# ProPrj_Fallout_card_2026-06-26.net
KiCad netlist of a schematic drawn in EasyEDA Pro
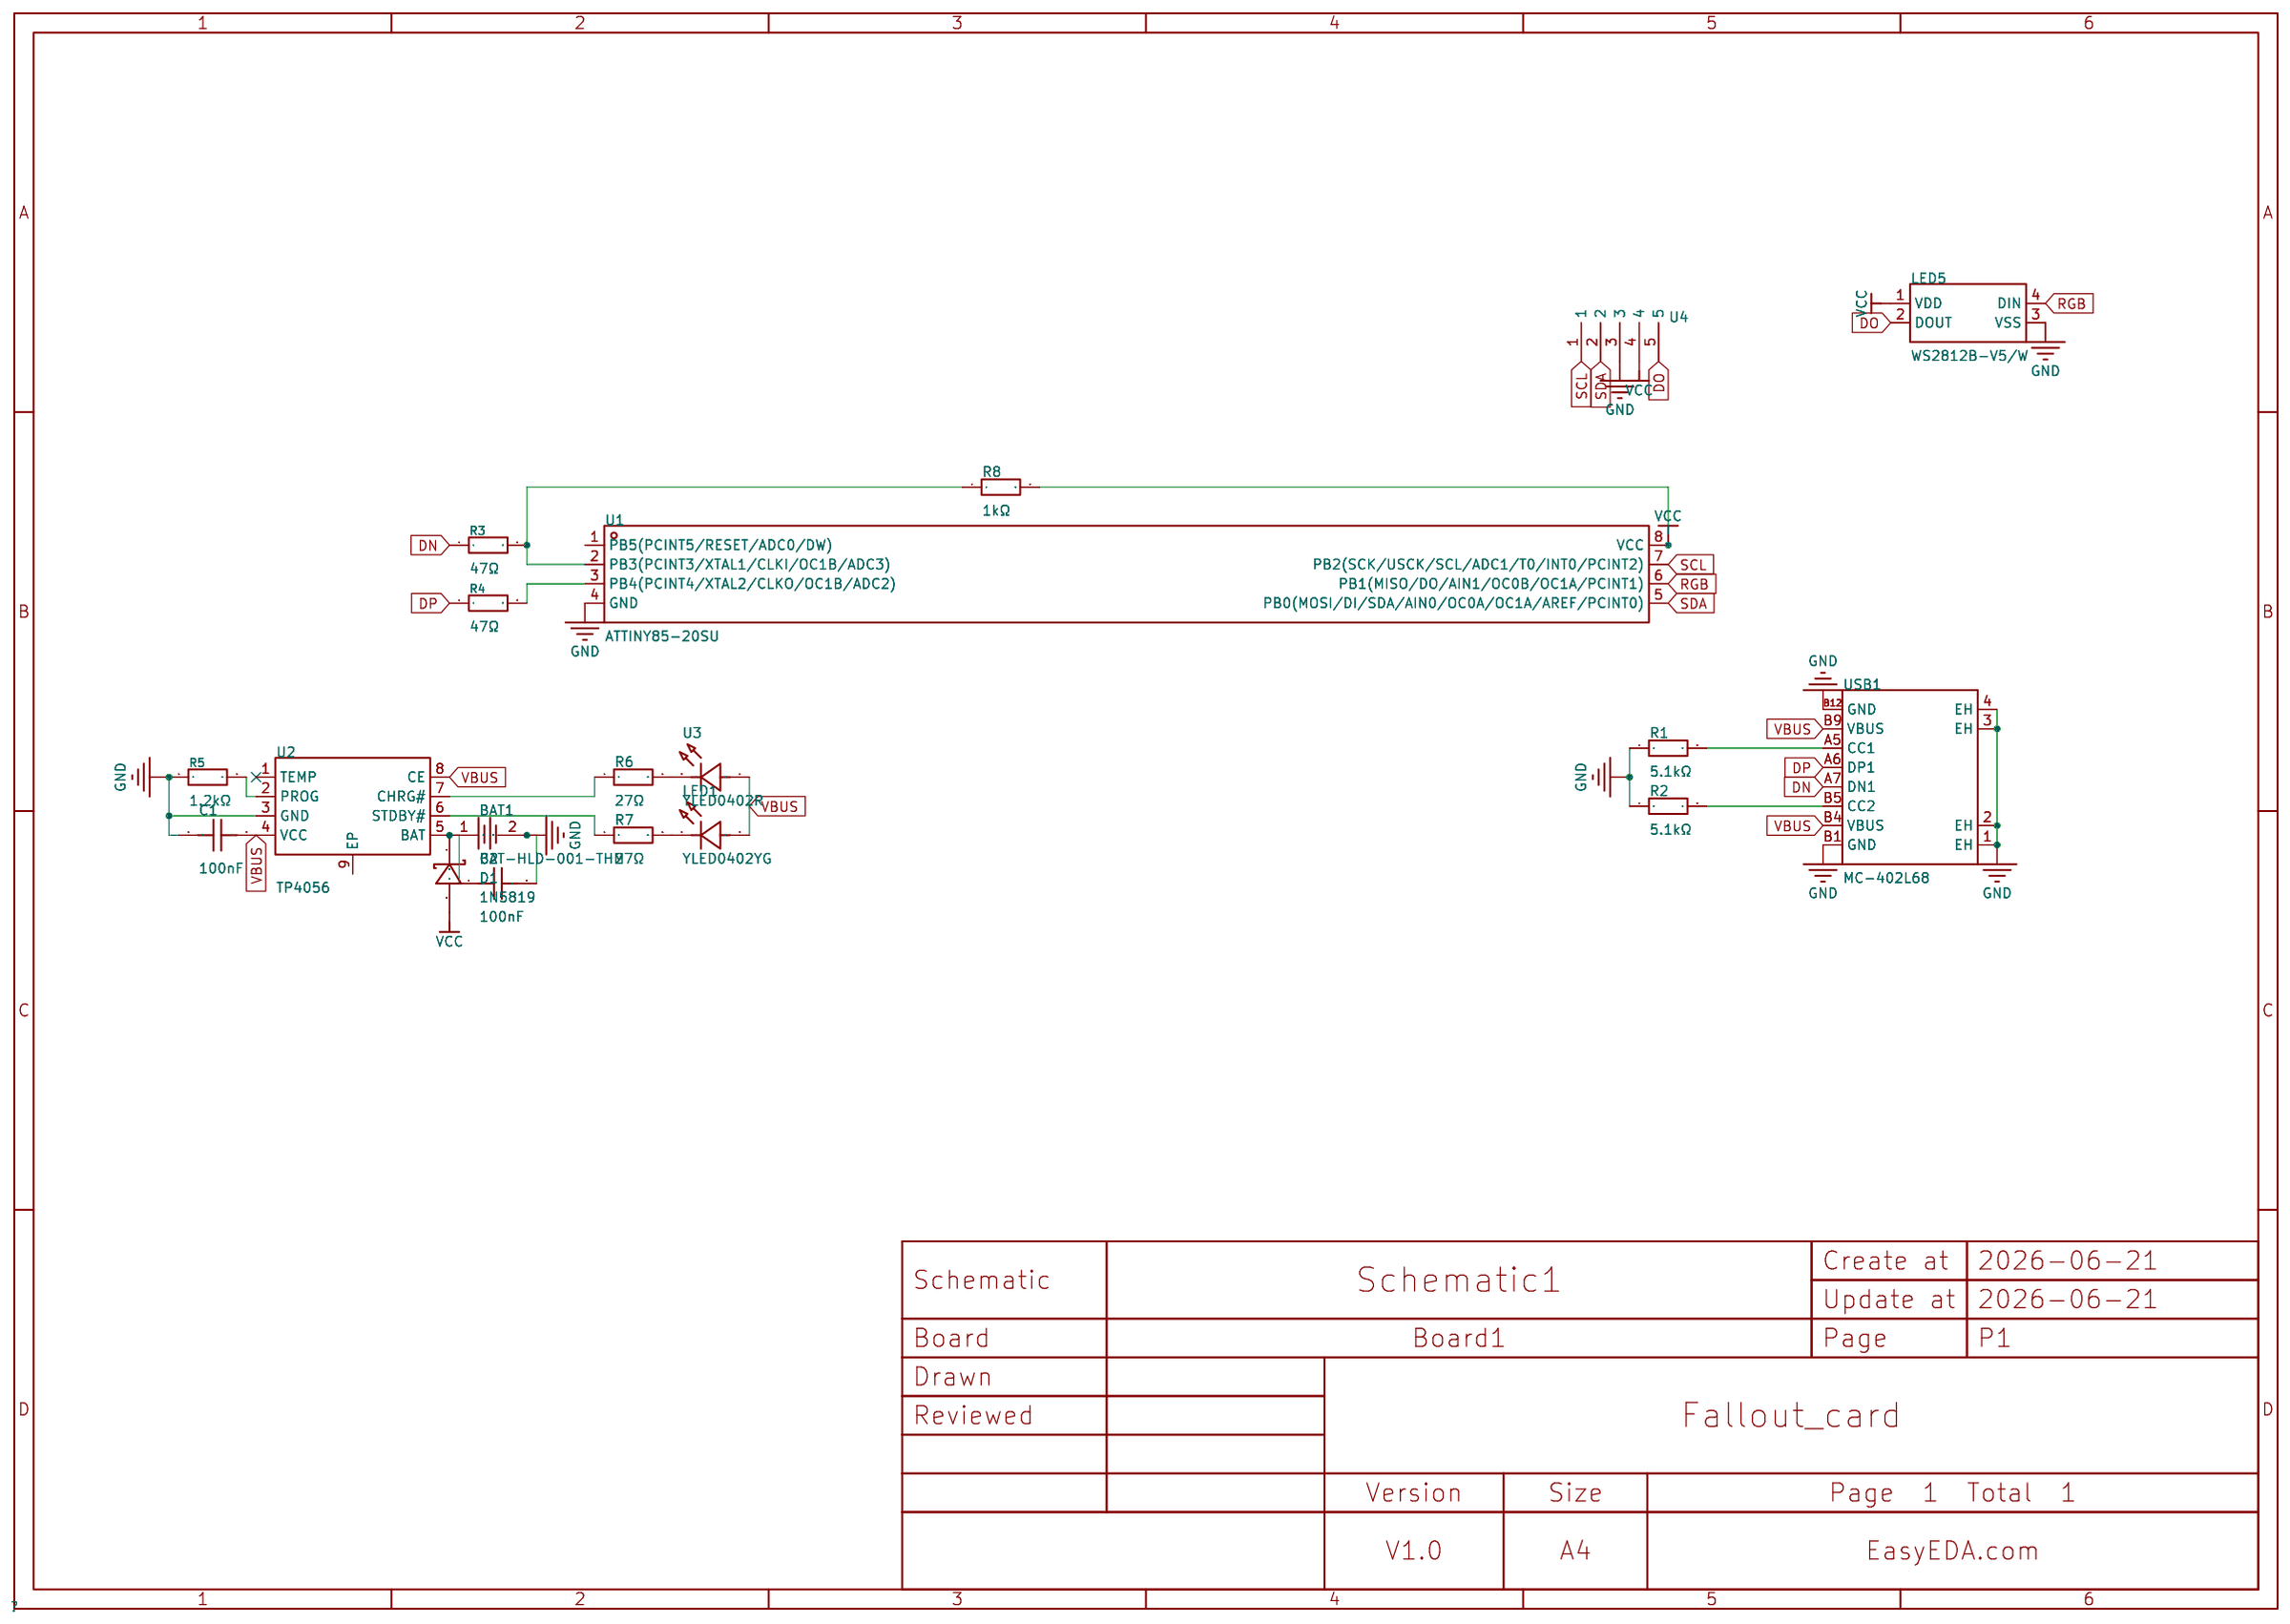
[diagram p0: schematic sheet]

(export (version "E")
  (design (tool "Eeschema 10.0.6"))
  (components
    (comp (ref "BAT1")
      (value "BAT-HLD-001-THM")
      (footprint "easyedapro:BAT-TH_BAT-HLD-001-THM_1")
      (fields (field (name "Manufacturer") "TE Connectivity(泰科电子)"))
      (libsource (lib "easyedapro") (part "BAT-HLD-001-THM"))
    )
    (comp (ref "C1")
      (value "100nF")
      (footprint "easyedapro:C0402")
      (fields
        (field (name "Manufacturer Part") "GRM155B31H104KE14D")
        (field (name "Manufacturer") "muRata(村田)")
      )
      (libsource (lib "easyedapro") (part "GRM155B31H104KE14D"))
    )
    (comp (ref "C2")
      (value "100nF")
      (footprint "easyedapro:C0402")
      (fields
        (field (name "Manufacturer Part") "GRM155B31H104KE14D")
        (field (name "Manufacturer") "muRata(村田)")
      )
      (libsource (lib "easyedapro") (part "GRM155B31H104KE14D"))
    )
    (comp (ref "D1")
      (value "1N5819")
      (footprint "easyedapro:SMA_L4.4-W2.6-LS5.0-RD")
      (fields (field (name "Manufacturer") "KEXIN(科信)"))
      (libsource (lib "easyedapro") (part "1N5819_C437199"))
    )
    (comp (ref "LED1")
      (value "YLED0402YG")
      (footprint "easyedapro:LED0402-RD")
      (fields (field (name "Manufacturer") "YONGYUTAI(永裕泰)"))
      (libsource (lib "easyedapro") (part "YLED0402YG"))
    )
    (comp (ref "LED5")
      (value "WS2812B-V5/W")
      (footprint "easyedapro:LED-SMD_4P-L5.0-W5.0-TL-1")
      (fields (field (name "Manufacturer") "worldsemi"))
      (libsource (lib "easyedapro") (part "WS2812B-V5/W"))
    )
    (comp (ref "R1")
      (value "5.1kΩ")
      (footprint "easyedapro:R0402")
      (fields (field (name "Manufacturer Part") "RMC04025.1K5%N") (field (name "Manufacturer") "Tyohm(幸亚电阻)"))
      (libsource (lib "easyedapro") (part "RMC04025.1K5%N"))
    )
    (comp (ref "R2")
      (value "5.1kΩ")
      (footprint "easyedapro:R0402")
      (fields (field (name "Manufacturer Part") "RMC04025.1K5%N") (field (name "Manufacturer") "Tyohm(幸亚电阻)"))
      (libsource (lib "easyedapro") (part "RMC04025.1K5%N"))
    )
    (comp (ref "R3")
      (value "47Ω")
      (footprint "easyedapro:R0402")
      (fields (field (name "Manufacturer Part") "RTT0247R0FTH") (field (name "Manufacturer") "RALEC(旺诠)"))
      (libsource (lib "easyedapro") (part "RTT0247R0FTH"))
    )
    (comp (ref "R4")
      (value "47Ω")
      (footprint "easyedapro:R0402")
      (fields (field (name "Manufacturer Part") "RTT0247R0FTH") (field (name "Manufacturer") "RALEC(旺诠)"))
      (libsource (lib "easyedapro") (part "RTT0247R0FTH"))
    )
    (comp (ref "R5")
      (value "1.2kΩ")
      (footprint "easyedapro:R0402")
      (fields (field (name "Manufacturer Part") "RMC04021.2K5%N") (field (name "Manufacturer") "Tyohm(幸亚电阻)"))
      (libsource (lib "easyedapro") (part "RMC04021.2K5%N"))
    )
    (comp (ref "R6")
      (value "27Ω")
      (footprint "easyedapro:R0402")
      (fields (field (name "Manufacturer Part") "RMS04JT270") (field (name "Manufacturer") "大毅科技"))
      (libsource (lib "easyedapro") (part "RMS04JT270"))
    )
    (comp (ref "R7")
      (value "27Ω")
      (footprint "easyedapro:R0402")
      (fields (field (name "Manufacturer Part") "RMS04JT270") (field (name "Manufacturer") "大毅科技"))
      (libsource (lib "easyedapro") (part "RMS04JT270"))
    )
    (comp (ref "R8")
      (value "1kΩ")
      (footprint "easyedapro:R0402")
      (fields (field (name "Manufacturer Part") "RT0402FRE071KL") (field (name "Manufacturer") "YAGEO(国巨)"))
      (libsource (lib "easyedapro") (part "RT0402FRE071KL"))
    )
    (comp (ref "U1")
      (value "ATTINY85-20SU")
      (footprint "easyedapro:SOIC-8_L5.3-W5.3-P1.27-LS8.0-BL")
      (fields (field (name "Manufacturer") "MICROCHIP(美国微芯)"))
      (libsource (lib "easyedapro") (part "ATTINY85-20SU_C31540447"))
    )
    (comp (ref "U2")
      (value "TP4056")
      (footprint "easyedapro:ESOP-8_L4.9-W3.9-P1.27-LS6.0-BL-EP-1")
      (fields (field (name "Manufacturer") "HICHON(海川)"))
      (libsource (lib "easyedapro") (part "TP4056_C49045948"))
    )
    (comp (ref "U3")
      (value "YLED0402R")
      (footprint "easyedapro:LED0402-R-RD")
      (fields (field (name "Manufacturer") "YONGYUTAI(永裕泰)"))
      (libsource (lib "easyedapro") (part "YLED0402R"))
    )
    (comp (ref "U4")
      (value "~")
      (footprint "easyedapro:PAD'S")
      (libsource (lib "easyedapro") (part "pad's for tiny mcu"))
    )
    (comp (ref "USB1")
      (value "MC-402L68")
      (footprint "easyedapro:USB-C-SMD_MC-402L68")
      (fields (field (name "Manufacturer") "HANBO(汉博)"))
      (libsource (lib "easyedapro") (part "MC-402L68"))
    )
  )
  (nets
    (net (code "1") (name "DN") (class "Default")
      (node (ref "R3") (pin "1") (pinfunction "1_1") (pintype "input"))
      (node (ref "USB1") (pin "A7") (pinfunction "DN1_A7") (pintype "unspecified"))
    )
    (net (code "2") (name "DO") (class "Default")
      (node (ref "LED5") (pin "2") (pinfunction "DOUT_2") (pintype "unspecified"))
      (node (ref "U4") (pin "5") (pinfunction "5_5") (pintype "unspecified"))
    )
    (net (code "3") (name "DP") (class "Default")
      (node (ref "R4") (pin "1") (pinfunction "1_1") (pintype "input"))
      (node (ref "USB1") (pin "A6") (pinfunction "DP1_A6") (pintype "unspecified"))
    )
    (net (code "4") (name "GND") (class "Default")
      (node (ref "BAT1") (pin "2") (pinfunction "2_2") (pintype "input"))
      (node (ref "C1") (pin "1") (pinfunction "1_1") (pintype "unspecified"))
      (node (ref "C2") (pin "2") (pinfunction "2_2") (pintype "unspecified"))
      (node (ref "LED5") (pin "3") (pinfunction "VSS_3") (pintype "unspecified"))
      (node (ref "R1") (pin "1") (pinfunction "1_1") (pintype "unspecified"))
      (node (ref "R2") (pin "1") (pinfunction "1_1") (pintype "unspecified"))
      (node (ref "R5") (pin "1") (pinfunction "1_1") (pintype "input"))
      (node (ref "U1") (pin "4") (pinfunction "GND_4") (pintype "unspecified"))
      (node (ref "U2") (pin "3") (pinfunction "GND_3") (pintype "unspecified"))
      (node (ref "U4") (pin "3") (pinfunction "3_3") (pintype "unspecified"))
      (node (ref "USB1") (pin "1") (pinfunction "EH_1") (pintype "unspecified"))
      (node (ref "USB1") (pin "2") (pinfunction "EH_2") (pintype "unspecified"))
      (node (ref "USB1") (pin "3") (pinfunction "EH_3") (pintype "unspecified"))
      (node (ref "USB1") (pin "4") (pinfunction "EH_4") (pintype "unspecified"))
      (node (ref "USB1") (pin "B1") (pinfunction "GND_B1") (pintype "unspecified"))
      (node (ref "USB1") (pin "B12") (pinfunction "GND_B12") (pintype "unspecified"))
    )
    (net (code "5") (name "Net-(D1-C)") (class "Default")
      (node (ref "BAT1") (pin "1") (pinfunction "1_1") (pintype "input"))
      (node (ref "C2") (pin "1") (pinfunction "1_1") (pintype "unspecified"))
      (node (ref "D1") (pin "1") (pinfunction "C_1") (pintype "unspecified"))
      (node (ref "U2") (pin "5") (pinfunction "BAT_5") (pintype "unspecified"))
    )
    (net (code "6") (name "Net-(LED1-K)") (class "Default")
      (node (ref "LED1") (pin "1") (pinfunction "K_1") (pintype "unspecified"))
      (node (ref "R7") (pin "2") (pinfunction "2_2") (pintype "input"))
    )
    (net (code "7") (name "Net-(U1-PB3(PCINT3{slash}XTAL1{slash}CLKI{slash}OC1B{slash}ADC3))") (class "Default")
      (node (ref "R3") (pin "2") (pinfunction "2_2") (pintype "input"))
      (node (ref "R8") (pin "1") (pinfunction "1_1") (pintype "unspecified"))
      (node (ref "U1") (pin "2") (pinfunction "PB3(PCINT3/XTAL1/CLKI/OC1B/ADC3)_2") (pintype "unspecified"))
    )
    (net (code "8") (name "Net-(U1-PB4(PCINT4{slash}XTAL2{slash}CLKO{slash}OC1B{slash}ADC2))") (class "Default")
      (node (ref "R4") (pin "2") (pinfunction "2_2") (pintype "input"))
      (node (ref "U1") (pin "3") (pinfunction "PB4(PCINT4/XTAL2/CLKO/OC1B/ADC2)_3") (pintype "unspecified"))
    )
    (net (code "9") (name "Net-(U2-CHRG#)") (class "Default")
      (node (ref "R6") (pin "1") (pinfunction "1_1") (pintype "input"))
      (node (ref "U2") (pin "7") (pinfunction "CHRG#_7") (pintype "unspecified"))
    )
    (net (code "10") (name "Net-(U2-PROG)") (class "Default")
      (node (ref "R5") (pin "2") (pinfunction "2_2") (pintype "input"))
      (node (ref "U2") (pin "2") (pinfunction "PROG_2") (pintype "unspecified"))
    )
    (net (code "11") (name "Net-(U2-STDBY#)") (class "Default")
      (node (ref "R7") (pin "1") (pinfunction "1_1") (pintype "input"))
      (node (ref "U2") (pin "6") (pinfunction "STDBY#_6") (pintype "unspecified"))
    )
    (net (code "12") (name "Net-(U3-K)") (class "Default")
      (node (ref "R6") (pin "2") (pinfunction "2_2") (pintype "input"))
      (node (ref "U3") (pin "2") (pinfunction "K_2") (pintype "unspecified"))
    )
    (net (code "13") (name "Net-(USB1-CC1)") (class "Default")
      (node (ref "R1") (pin "2") (pinfunction "2_2") (pintype "unspecified"))
      (node (ref "USB1") (pin "A5") (pinfunction "CC1_A5") (pintype "unspecified"))
    )
    (net (code "14") (name "Net-(USB1-CC2)") (class "Default")
      (node (ref "R2") (pin "2") (pinfunction "2_2") (pintype "unspecified"))
      (node (ref "USB1") (pin "B5") (pinfunction "CC2_B5") (pintype "unspecified"))
    )
    (net (code "15") (name "RGB") (class "Default")
      (node (ref "LED5") (pin "4") (pinfunction "DIN_4") (pintype "unspecified"))
      (node (ref "U1") (pin "6") (pinfunction "PB1(MISO/DO/AIN1/OC0B/OC1A/PCINT1)_6") (pintype "unspecified"))
    )
    (net (code "16") (name "SCL") (class "Default")
      (node (ref "U1") (pin "7") (pinfunction "PB2(SCK/USCK/SCL/ADC1/T0/INT0/PCINT2)_7") (pintype "unspecified"))
      (node (ref "U4") (pin "1") (pinfunction "1_1") (pintype "unspecified"))
    )
    (net (code "17") (name "SDA") (class "Default")
      (node (ref "U1") (pin "5") (pinfunction "PB0(MOSI/DI/SDA/AIN0/OC0A/OC1A/AREF/PCINT0)_5") (pintype "unspecified"))
      (node (ref "U4") (pin "2") (pinfunction "2_2") (pintype "unspecified"))
    )
    (net (code "18") (name "VBUS") (class "Default")
      (node (ref "C1") (pin "2") (pinfunction "2_2") (pintype "unspecified"))
      (node (ref "LED1") (pin "2") (pinfunction "A_2") (pintype "unspecified"))
      (node (ref "U2") (pin "4") (pinfunction "VCC_4") (pintype "unspecified"))
      (node (ref "U2") (pin "8") (pinfunction "CE_8") (pintype "unspecified"))
      (node (ref "U3") (pin "1") (pinfunction "A_1") (pintype "unspecified"))
      (node (ref "USB1") (pin "B4") (pinfunction "VBUS_B4") (pintype "unspecified"))
      (node (ref "USB1") (pin "B9") (pinfunction "VBUS_B9") (pintype "unspecified"))
    )
    (net (code "19") (name "VCC") (class "Default")
      (node (ref "D1") (pin "2") (pinfunction "A_2") (pintype "unspecified"))
      (node (ref "LED5") (pin "1") (pinfunction "VDD_1") (pintype "unspecified"))
      (node (ref "R8") (pin "2") (pinfunction "2_2") (pintype "unspecified"))
      (node (ref "U1") (pin "8") (pinfunction "VCC_8") (pintype "unspecified"))
      (node (ref "U4") (pin "4") (pinfunction "4_4") (pintype "unspecified"))
    )
    (net (code "20") (name "unconnected-(U1-PB5(PCINT5{slash}RESET{slash}ADC0{slash}DW)-Pad1)") (class "Default")
      (node (ref "U1") (pin "1") (pinfunction "PB5(PCINT5/RESET/ADC0/DW)_1") (pintype "unspecified"))
    )
    (net (code "21") (name "unconnected-(U2-EP-Pad9)") (class "Default")
      (node (ref "U2") (pin "9") (pinfunction "EP_9") (pintype "unspecified"))
    )
    (net (code "22") (name "unconnected-(U2-TEMP-Pad1)") (class "Default")
      (node (ref "U2") (pin "1") (pinfunction "TEMP_1") (pintype "unspecified+no_connect"))
    )
  )
)
